# BBB_Breakout.net
KiCad netlist of a schematic drawn in EAGLE
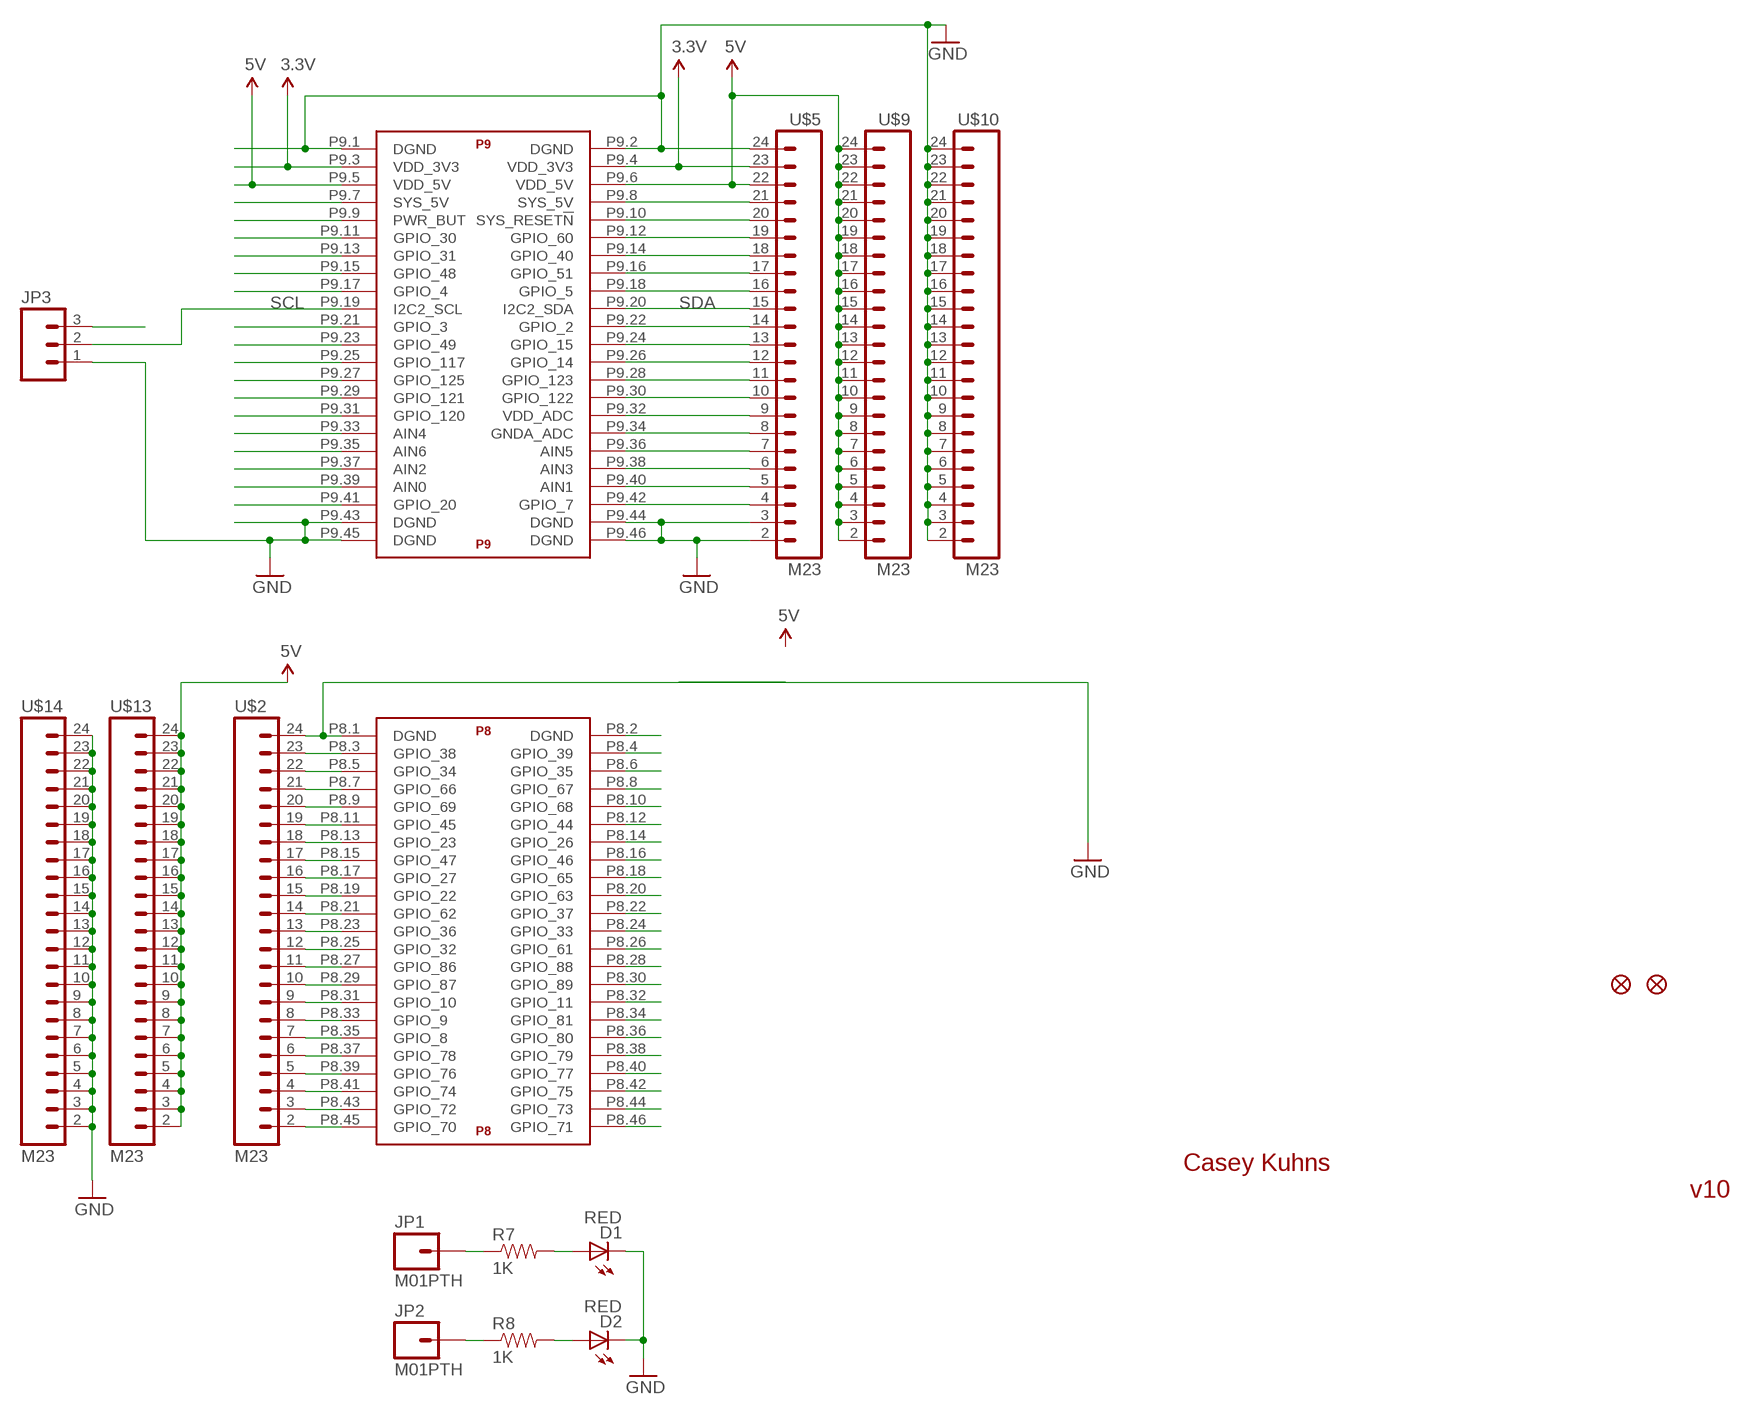
[diagram p0: schematic, sheet 1]

(export (version "E")
  (design (tool "Eeschema 10.0.6"))
  (components
    (comp (ref "D1")
      (value "RED")
      (footprint "eagle-import:LED-0603")
      (libsource (lib "eagle-import") (part "LED-RED0603"))
    )
    (comp (ref "D2")
      (value "RED")
      (footprint "eagle-import:LED-0603")
      (libsource (lib "eagle-import") (part "LED-RED0603"))
    )
    (comp (ref "FID1")
      (value "FIDUCIAL1X2")
      (footprint "eagle-import:FIDUCIAL-1X2")
      (libsource (lib "eagle-import") (part "FIDUCIAL1X2"))
    )
    (comp (ref "FID2")
      (value "FIDUCIAL1X2")
      (footprint "eagle-import:FIDUCIAL-1X2")
      (libsource (lib "eagle-import") (part "FIDUCIAL1X2"))
    )
    (comp (ref "JP1")
      (value "M01PTH")
      (footprint "eagle-import:1X01")
      (libsource (lib "eagle-import") (part "M01PTH"))
    )
    (comp (ref "JP2")
      (value "M01PTH")
      (footprint "eagle-import:1X01")
      (libsource (lib "eagle-import") (part "M01PTH"))
    )
    (comp (ref "JP3")
      (value "M03PTH")
      (footprint "eagle-import:1X03")
      (libsource (lib "eagle-import") (part "M03PTH"))
    )
    (comp (ref "R7")
      (value "1K")
      (footprint "eagle-import:0603-RES")
      (libsource (lib "eagle-import") (part "1KOHM1/10W1%(0603)"))
    )
    (comp (ref "R8")
      (value "1K")
      (footprint "eagle-import:0603-RES")
      (libsource (lib "eagle-import") (part "1KOHM1/10W1%(0603)"))
    )
    (comp (ref "U$1")
      (value "BEAGLE_BONE_BLACK_CAPE")
      (footprint "eagle-import:BEAGLE_BONE_BLACK_CAPE")
      (libsource (lib "eagle-import") (part "BEAGLE_BONE_BLACK_CAPE"))
    )
    (comp (ref "U$2")
      (value "M23")
      (footprint "eagle-import:1X23")
      (libsource (lib "eagle-import") (part "M23"))
    )
    (comp (ref "U$5")
      (value "M23")
      (footprint "eagle-import:1X23")
      (libsource (lib "eagle-import") (part "M23"))
    )
    (comp (ref "U$9")
      (value "M23")
      (footprint "eagle-import:1X23")
      (libsource (lib "eagle-import") (part "M23"))
    )
    (comp (ref "U$10")
      (value "M23")
      (footprint "eagle-import:1X23")
      (libsource (lib "eagle-import") (part "M23"))
    )
    (comp (ref "U$13")
      (value "M23")
      (footprint "eagle-import:1X23")
      (libsource (lib "eagle-import") (part "M23"))
    )
    (comp (ref "U$14")
      (value "M23")
      (footprint "eagle-import:1X23")
      (libsource (lib "eagle-import") (part "M23"))
    )
  )
  (nets
    (net (code "1") (name "/SCL") (class "Default")
      (node (ref "JP3") (pin "2") (pinfunction "2_2") (pintype "passive"))
      (node (ref "U$1") (pin "P9.19") (pinfunction "I2C2_SCL_P9.19") (pintype "bidirectional"))
    )
    (net (code "2") (name "/SDA") (class "Default")
      (node (ref "JP3") (pin "3") (pinfunction "3_3") (pintype "passive"))
      (node (ref "U$1") (pin "P9.20") (pinfunction "I2C2_SDA_P9.20") (pintype "bidirectional"))
      (node (ref "U$5") (pin "15") (pinfunction "15_15") (pintype "passive"))
    )
    (net (code "3") (name "3.3V") (class "Default")
      (node (ref "U$1") (pin "P9.3") (pinfunction "VDD_3V3_P9.3") (pintype "bidirectional"))
      (node (ref "U$1") (pin "P9.4") (pinfunction "VDD_3V3_P9.4") (pintype "bidirectional"))
      (node (ref "U$5") (pin "23") (pinfunction "23_23") (pintype "passive"))
    )
    (net (code "4") (name "5V") (class "Default")
      (node (ref "U$1") (pin "P9.5") (pinfunction "VDD_5V_P9.5") (pintype "bidirectional"))
      (node (ref "U$1") (pin "P9.6") (pinfunction "VDD_5V_P9.6") (pintype "bidirectional"))
      (node (ref "U$13") (pin "10") (pinfunction "10_10") (pintype "passive"))
      (node (ref "U$13") (pin "11") (pinfunction "11_11") (pintype "passive"))
      (node (ref "U$13") (pin "12") (pinfunction "12_12") (pintype "passive"))
      (node (ref "U$13") (pin "13") (pinfunction "13_13") (pintype "passive"))
      (node (ref "U$13") (pin "14") (pinfunction "14_14") (pintype "passive"))
      (node (ref "U$13") (pin "15") (pinfunction "15_15") (pintype "passive"))
      (node (ref "U$13") (pin "16") (pinfunction "16_16") (pintype "passive"))
      (node (ref "U$13") (pin "17") (pinfunction "17_17") (pintype "passive"))
      (node (ref "U$13") (pin "18") (pinfunction "18_18") (pintype "passive"))
      (node (ref "U$13") (pin "19") (pinfunction "19_19") (pintype "passive"))
      (node (ref "U$13") (pin "2") (pinfunction "2_2") (pintype "passive"))
      (node (ref "U$13") (pin "20") (pinfunction "20_20") (pintype "passive"))
      (node (ref "U$13") (pin "21") (pinfunction "21_21") (pintype "passive"))
      (node (ref "U$13") (pin "22") (pinfunction "22_22") (pintype "passive"))
      (node (ref "U$13") (pin "23") (pinfunction "23_23") (pintype "passive"))
      (node (ref "U$13") (pin "24") (pinfunction "24_24") (pintype "passive"))
      (node (ref "U$13") (pin "3") (pinfunction "3_3") (pintype "passive"))
      (node (ref "U$13") (pin "4") (pinfunction "4_4") (pintype "passive"))
      (node (ref "U$13") (pin "5") (pinfunction "5_5") (pintype "passive"))
      (node (ref "U$13") (pin "6") (pinfunction "6_6") (pintype "passive"))
      (node (ref "U$13") (pin "7") (pinfunction "7_7") (pintype "passive"))
      (node (ref "U$13") (pin "8") (pinfunction "8_8") (pintype "passive"))
      (node (ref "U$13") (pin "9") (pinfunction "9_9") (pintype "passive"))
      (node (ref "U$5") (pin "22") (pinfunction "22_22") (pintype "passive"))
      (node (ref "U$9") (pin "10") (pinfunction "10_10") (pintype "passive"))
      (node (ref "U$9") (pin "11") (pinfunction "11_11") (pintype "passive"))
      (node (ref "U$9") (pin "12") (pinfunction "12_12") (pintype "passive"))
      (node (ref "U$9") (pin "13") (pinfunction "13_13") (pintype "passive"))
      (node (ref "U$9") (pin "14") (pinfunction "14_14") (pintype "passive"))
      (node (ref "U$9") (pin "15") (pinfunction "15_15") (pintype "passive"))
      (node (ref "U$9") (pin "16") (pinfunction "16_16") (pintype "passive"))
      (node (ref "U$9") (pin "17") (pinfunction "17_17") (pintype "passive"))
      (node (ref "U$9") (pin "18") (pinfunction "18_18") (pintype "passive"))
      (node (ref "U$9") (pin "19") (pinfunction "19_19") (pintype "passive"))
      (node (ref "U$9") (pin "2") (pinfunction "2_2") (pintype "passive"))
      (node (ref "U$9") (pin "20") (pinfunction "20_20") (pintype "passive"))
      (node (ref "U$9") (pin "21") (pinfunction "21_21") (pintype "passive"))
      (node (ref "U$9") (pin "22") (pinfunction "22_22") (pintype "passive"))
      (node (ref "U$9") (pin "23") (pinfunction "23_23") (pintype "passive"))
      (node (ref "U$9") (pin "24") (pinfunction "24_24") (pintype "passive"))
      (node (ref "U$9") (pin "3") (pinfunction "3_3") (pintype "passive"))
      (node (ref "U$9") (pin "4") (pinfunction "4_4") (pintype "passive"))
      (node (ref "U$9") (pin "5") (pinfunction "5_5") (pintype "passive"))
      (node (ref "U$9") (pin "6") (pinfunction "6_6") (pintype "passive"))
      (node (ref "U$9") (pin "7") (pinfunction "7_7") (pintype "passive"))
      (node (ref "U$9") (pin "8") (pinfunction "8_8") (pintype "passive"))
      (node (ref "U$9") (pin "9") (pinfunction "9_9") (pintype "passive"))
    )
    (net (code "5") (name "GND") (class "Default")
      (node (ref "D1") (pin "C") (pinfunction "C_C") (pintype "passive"))
      (node (ref "D2") (pin "C") (pinfunction "C_C") (pintype "passive"))
      (node (ref "JP3") (pin "1") (pinfunction "1_1") (pintype "passive"))
      (node (ref "U$1") (pin "P8.1") (pinfunction "DGND_P8.1") (pintype "bidirectional"))
      (node (ref "U$1") (pin "P9.1") (pinfunction "DGND_P9.1") (pintype "bidirectional"))
      (node (ref "U$1") (pin "P9.2") (pinfunction "DGND_P9.2") (pintype "bidirectional"))
      (node (ref "U$1") (pin "P9.43") (pinfunction "DGND_P9.43") (pintype "bidirectional"))
      (node (ref "U$1") (pin "P9.44") (pinfunction "DGND_P9.44") (pintype "bidirectional"))
      (node (ref "U$1") (pin "P9.45") (pinfunction "DGND_P9.45") (pintype "bidirectional"))
      (node (ref "U$1") (pin "P9.46") (pinfunction "DGND_P9.46") (pintype "bidirectional"))
      (node (ref "U$10") (pin "10") (pinfunction "10_10") (pintype "passive"))
      (node (ref "U$10") (pin "11") (pinfunction "11_11") (pintype "passive"))
      (node (ref "U$10") (pin "12") (pinfunction "12_12") (pintype "passive"))
      (node (ref "U$10") (pin "13") (pinfunction "13_13") (pintype "passive"))
      (node (ref "U$10") (pin "14") (pinfunction "14_14") (pintype "passive"))
      (node (ref "U$10") (pin "15") (pinfunction "15_15") (pintype "passive"))
      (node (ref "U$10") (pin "16") (pinfunction "16_16") (pintype "passive"))
      (node (ref "U$10") (pin "17") (pinfunction "17_17") (pintype "passive"))
      (node (ref "U$10") (pin "18") (pinfunction "18_18") (pintype "passive"))
      (node (ref "U$10") (pin "19") (pinfunction "19_19") (pintype "passive"))
      (node (ref "U$10") (pin "2") (pinfunction "2_2") (pintype "passive"))
      (node (ref "U$10") (pin "20") (pinfunction "20_20") (pintype "passive"))
      (node (ref "U$10") (pin "21") (pinfunction "21_21") (pintype "passive"))
      (node (ref "U$10") (pin "22") (pinfunction "22_22") (pintype "passive"))
      (node (ref "U$10") (pin "23") (pinfunction "23_23") (pintype "passive"))
      (node (ref "U$10") (pin "24") (pinfunction "24_24") (pintype "passive"))
      (node (ref "U$10") (pin "3") (pinfunction "3_3") (pintype "passive"))
      (node (ref "U$10") (pin "4") (pinfunction "4_4") (pintype "passive"))
      (node (ref "U$10") (pin "5") (pinfunction "5_5") (pintype "passive"))
      (node (ref "U$10") (pin "6") (pinfunction "6_6") (pintype "passive"))
      (node (ref "U$10") (pin "7") (pinfunction "7_7") (pintype "passive"))
      (node (ref "U$10") (pin "8") (pinfunction "8_8") (pintype "passive"))
      (node (ref "U$10") (pin "9") (pinfunction "9_9") (pintype "passive"))
      (node (ref "U$14") (pin "10") (pinfunction "10_10") (pintype "passive"))
      (node (ref "U$14") (pin "11") (pinfunction "11_11") (pintype "passive"))
      (node (ref "U$14") (pin "12") (pinfunction "12_12") (pintype "passive"))
      (node (ref "U$14") (pin "13") (pinfunction "13_13") (pintype "passive"))
      (node (ref "U$14") (pin "14") (pinfunction "14_14") (pintype "passive"))
      (node (ref "U$14") (pin "15") (pinfunction "15_15") (pintype "passive"))
      (node (ref "U$14") (pin "16") (pinfunction "16_16") (pintype "passive"))
      (node (ref "U$14") (pin "17") (pinfunction "17_17") (pintype "passive"))
      (node (ref "U$14") (pin "18") (pinfunction "18_18") (pintype "passive"))
      (node (ref "U$14") (pin "19") (pinfunction "19_19") (pintype "passive"))
      (node (ref "U$14") (pin "2") (pinfunction "2_2") (pintype "passive"))
      (node (ref "U$14") (pin "20") (pinfunction "20_20") (pintype "passive"))
      (node (ref "U$14") (pin "21") (pinfunction "21_21") (pintype "passive"))
      (node (ref "U$14") (pin "22") (pinfunction "22_22") (pintype "passive"))
      (node (ref "U$14") (pin "23") (pinfunction "23_23") (pintype "passive"))
      (node (ref "U$14") (pin "24") (pinfunction "24_24") (pintype "passive"))
      (node (ref "U$14") (pin "3") (pinfunction "3_3") (pintype "passive"))
      (node (ref "U$14") (pin "4") (pinfunction "4_4") (pintype "passive"))
      (node (ref "U$14") (pin "5") (pinfunction "5_5") (pintype "passive"))
      (node (ref "U$14") (pin "6") (pinfunction "6_6") (pintype "passive"))
      (node (ref "U$14") (pin "7") (pinfunction "7_7") (pintype "passive"))
      (node (ref "U$14") (pin "8") (pinfunction "8_8") (pintype "passive"))
      (node (ref "U$14") (pin "9") (pinfunction "9_9") (pintype "passive"))
      (node (ref "U$2") (pin "24") (pinfunction "24_24") (pintype "passive"))
      (node (ref "U$5") (pin "2") (pinfunction "2_2") (pintype "passive"))
      (node (ref "U$5") (pin "24") (pinfunction "24_24") (pintype "passive"))
      (node (ref "U$5") (pin "3") (pinfunction "3_3") (pintype "passive"))
    )
    (net (code "6") (name "Net-(D1-PadA)") (class "Default")
      (node (ref "D1") (pin "A") (pinfunction "A_A") (pintype "passive"))
      (node (ref "R7") (pin "2") (pinfunction "2_2") (pintype "passive"))
    )
    (net (code "7") (name "Net-(D2-PadA)") (class "Default")
      (node (ref "D2") (pin "A") (pinfunction "A_A") (pintype "passive"))
      (node (ref "R8") (pin "2") (pinfunction "2_2") (pintype "passive"))
    )
    (net (code "8") (name "Net-(JP1-Pad1)") (class "Default")
      (node (ref "JP1") (pin "1") (pinfunction "1_1") (pintype "passive"))
      (node (ref "R7") (pin "1") (pinfunction "1_1") (pintype "passive"))
    )
    (net (code "9") (name "Net-(JP2-Pad1)") (class "Default")
      (node (ref "JP2") (pin "1") (pinfunction "1_1") (pintype "passive"))
      (node (ref "R8") (pin "1") (pinfunction "1_1") (pintype "passive"))
    )
    (net (code "10") (name "Net-(U$1A-GPIO_8)") (class "Default")
      (node (ref "U$1") (pin "P8.35") (pinfunction "GPIO_8_P8.35") (pintype "bidirectional"))
      (node (ref "U$2") (pin "7") (pinfunction "7_7") (pintype "passive"))
    )
    (net (code "11") (name "Net-(U$1A-GPIO_9)") (class "Default")
      (node (ref "U$1") (pin "P8.33") (pinfunction "GPIO_9_P8.33") (pintype "bidirectional"))
      (node (ref "U$2") (pin "8") (pinfunction "8_8") (pintype "passive"))
    )
    (net (code "12") (name "Net-(U$1A-GPIO_10)") (class "Default")
      (node (ref "U$1") (pin "P8.31") (pinfunction "GPIO_10_P8.31") (pintype "bidirectional"))
      (node (ref "U$2") (pin "9") (pinfunction "9_9") (pintype "passive"))
    )
    (net (code "13") (name "Net-(U$1A-GPIO_22)") (class "Default")
      (node (ref "U$1") (pin "P8.19") (pinfunction "GPIO_22_P8.19") (pintype "bidirectional"))
      (node (ref "U$2") (pin "15") (pinfunction "15_15") (pintype "passive"))
    )
    (net (code "14") (name "Net-(U$1A-GPIO_23)") (class "Default")
      (node (ref "U$1") (pin "P8.13") (pinfunction "GPIO_23_P8.13") (pintype "bidirectional"))
      (node (ref "U$2") (pin "18") (pinfunction "18_18") (pintype "passive"))
    )
    (net (code "15") (name "Net-(U$1A-GPIO_27)") (class "Default")
      (node (ref "U$1") (pin "P8.17") (pinfunction "GPIO_27_P8.17") (pintype "bidirectional"))
      (node (ref "U$2") (pin "16") (pinfunction "16_16") (pintype "passive"))
    )
    (net (code "16") (name "Net-(U$1A-GPIO_32)") (class "Default")
      (node (ref "U$1") (pin "P8.25") (pinfunction "GPIO_32_P8.25") (pintype "bidirectional"))
      (node (ref "U$2") (pin "12") (pinfunction "12_12") (pintype "passive"))
    )
    (net (code "17") (name "Net-(U$1A-GPIO_34)") (class "Default")
      (node (ref "U$1") (pin "P8.5") (pinfunction "GPIO_34_P8.5") (pintype "bidirectional"))
      (node (ref "U$2") (pin "22") (pinfunction "22_22") (pintype "passive"))
    )
    (net (code "18") (name "Net-(U$1A-GPIO_36)") (class "Default")
      (node (ref "U$1") (pin "P8.23") (pinfunction "GPIO_36_P8.23") (pintype "bidirectional"))
      (node (ref "U$2") (pin "13") (pinfunction "13_13") (pintype "passive"))
    )
    (net (code "19") (name "Net-(U$1A-GPIO_38)") (class "Default")
      (node (ref "U$1") (pin "P8.3") (pinfunction "GPIO_38_P8.3") (pintype "bidirectional"))
      (node (ref "U$2") (pin "23") (pinfunction "23_23") (pintype "passive"))
    )
    (net (code "20") (name "Net-(U$1A-GPIO_45)") (class "Default")
      (node (ref "U$1") (pin "P8.11") (pinfunction "GPIO_45_P8.11") (pintype "bidirectional"))
      (node (ref "U$2") (pin "19") (pinfunction "19_19") (pintype "passive"))
    )
    (net (code "21") (name "Net-(U$1A-GPIO_47)") (class "Default")
      (node (ref "U$1") (pin "P8.15") (pinfunction "GPIO_47_P8.15") (pintype "bidirectional"))
      (node (ref "U$2") (pin "17") (pinfunction "17_17") (pintype "passive"))
    )
    (net (code "22") (name "Net-(U$1A-GPIO_62)") (class "Default")
      (node (ref "U$1") (pin "P8.21") (pinfunction "GPIO_62_P8.21") (pintype "bidirectional"))
      (node (ref "U$2") (pin "14") (pinfunction "14_14") (pintype "passive"))
    )
    (net (code "23") (name "Net-(U$1A-GPIO_66)") (class "Default")
      (node (ref "U$1") (pin "P8.7") (pinfunction "GPIO_66_P8.7") (pintype "bidirectional"))
      (node (ref "U$2") (pin "21") (pinfunction "21_21") (pintype "passive"))
    )
    (net (code "24") (name "Net-(U$1A-GPIO_69)") (class "Default")
      (node (ref "U$1") (pin "P8.9") (pinfunction "GPIO_69_P8.9") (pintype "bidirectional"))
      (node (ref "U$2") (pin "20") (pinfunction "20_20") (pintype "passive"))
    )
    (net (code "25") (name "Net-(U$1A-GPIO_70)") (class "Default")
      (node (ref "U$1") (pin "P8.45") (pinfunction "GPIO_70_P8.45") (pintype "bidirectional"))
      (node (ref "U$2") (pin "2") (pinfunction "2_2") (pintype "passive"))
    )
    (net (code "26") (name "Net-(U$1A-GPIO_72)") (class "Default")
      (node (ref "U$1") (pin "P8.43") (pinfunction "GPIO_72_P8.43") (pintype "bidirectional"))
      (node (ref "U$2") (pin "3") (pinfunction "3_3") (pintype "passive"))
    )
    (net (code "27") (name "Net-(U$1A-GPIO_74)") (class "Default")
      (node (ref "U$1") (pin "P8.41") (pinfunction "GPIO_74_P8.41") (pintype "bidirectional"))
      (node (ref "U$2") (pin "4") (pinfunction "4_4") (pintype "passive"))
    )
    (net (code "28") (name "Net-(U$1A-GPIO_76)") (class "Default")
      (node (ref "U$1") (pin "P8.39") (pinfunction "GPIO_76_P8.39") (pintype "bidirectional"))
      (node (ref "U$2") (pin "5") (pinfunction "5_5") (pintype "passive"))
    )
    (net (code "29") (name "Net-(U$1A-GPIO_78)") (class "Default")
      (node (ref "U$1") (pin "P8.37") (pinfunction "GPIO_78_P8.37") (pintype "bidirectional"))
      (node (ref "U$2") (pin "6") (pinfunction "6_6") (pintype "passive"))
    )
    (net (code "30") (name "Net-(U$1A-GPIO_86)") (class "Default")
      (node (ref "U$1") (pin "P8.27") (pinfunction "GPIO_86_P8.27") (pintype "bidirectional"))
      (node (ref "U$2") (pin "11") (pinfunction "11_11") (pintype "passive"))
    )
    (net (code "31") (name "Net-(U$1A-GPIO_87)") (class "Default")
      (node (ref "U$1") (pin "P8.29") (pinfunction "GPIO_87_P8.29") (pintype "bidirectional"))
      (node (ref "U$2") (pin "10") (pinfunction "10_10") (pintype "passive"))
    )
    (net (code "32") (name "Net-(U$1B-AIN1)") (class "Default")
      (node (ref "U$1") (pin "P9.40") (pinfunction "AIN1_P9.40") (pintype "bidirectional"))
      (node (ref "U$5") (pin "5") (pinfunction "5_5") (pintype "passive"))
    )
    (net (code "33") (name "Net-(U$1B-AIN3)") (class "Default")
      (node (ref "U$1") (pin "P9.38") (pinfunction "AIN3_P9.38") (pintype "bidirectional"))
      (node (ref "U$5") (pin "6") (pinfunction "6_6") (pintype "passive"))
    )
    (net (code "34") (name "Net-(U$1B-AIN5)") (class "Default")
      (node (ref "U$1") (pin "P9.36") (pinfunction "AIN5_P9.36") (pintype "bidirectional"))
      (node (ref "U$5") (pin "7") (pinfunction "7_7") (pintype "passive"))
    )
    (net (code "35") (name "Net-(U$1B-GNDA_ADC)") (class "Default")
      (node (ref "U$1") (pin "P9.34") (pinfunction "GNDA_ADC_P9.34") (pintype "bidirectional"))
      (node (ref "U$5") (pin "8") (pinfunction "8_8") (pintype "passive"))
    )
    (net (code "36") (name "Net-(U$1B-GPIO_2)") (class "Default")
      (node (ref "U$1") (pin "P9.22") (pinfunction "GPIO_2_P9.22") (pintype "bidirectional"))
      (node (ref "U$5") (pin "14") (pinfunction "14_14") (pintype "passive"))
    )
    (net (code "37") (name "Net-(U$1B-GPIO_5)") (class "Default")
      (node (ref "U$1") (pin "P9.18") (pinfunction "GPIO_5_P9.18") (pintype "bidirectional"))
      (node (ref "U$5") (pin "16") (pinfunction "16_16") (pintype "passive"))
    )
    (net (code "38") (name "Net-(U$1B-GPIO_7)") (class "Default")
      (node (ref "U$1") (pin "P9.42") (pinfunction "GPIO_7_P9.42") (pintype "bidirectional"))
      (node (ref "U$5") (pin "4") (pinfunction "4_4") (pintype "passive"))
    )
    (net (code "39") (name "Net-(U$1B-GPIO_14)") (class "Default")
      (node (ref "U$1") (pin "P9.26") (pinfunction "GPIO_14_P9.26") (pintype "bidirectional"))
      (node (ref "U$5") (pin "12") (pinfunction "12_12") (pintype "passive"))
    )
    (net (code "40") (name "Net-(U$1B-GPIO_15)") (class "Default")
      (node (ref "U$1") (pin "P9.24") (pinfunction "GPIO_15_P9.24") (pintype "bidirectional"))
      (node (ref "U$5") (pin "13") (pinfunction "13_13") (pintype "passive"))
    )
    (net (code "41") (name "Net-(U$1B-GPIO_40)") (class "Default")
      (node (ref "U$1") (pin "P9.14") (pinfunction "GPIO_40_P9.14") (pintype "bidirectional"))
      (node (ref "U$5") (pin "18") (pinfunction "18_18") (pintype "passive"))
    )
    (net (code "42") (name "Net-(U$1B-GPIO_51)") (class "Default")
      (node (ref "U$1") (pin "P9.16") (pinfunction "GPIO_51_P9.16") (pintype "bidirectional"))
      (node (ref "U$5") (pin "17") (pinfunction "17_17") (pintype "passive"))
    )
    (net (code "43") (name "Net-(U$1B-GPIO_60)") (class "Default")
      (node (ref "U$1") (pin "P9.12") (pinfunction "GPIO_60_P9.12") (pintype "bidirectional"))
      (node (ref "U$5") (pin "19") (pinfunction "19_19") (pintype "passive"))
    )
    (net (code "44") (name "Net-(U$1B-GPIO_122)") (class "Default")
      (node (ref "U$1") (pin "P9.30") (pinfunction "GPIO_122_P9.30") (pintype "bidirectional"))
      (node (ref "U$5") (pin "10") (pinfunction "10_10") (pintype "passive"))
    )
    (net (code "45") (name "Net-(U$1B-GPIO_123)") (class "Default")
      (node (ref "U$1") (pin "P9.28") (pinfunction "GPIO_123_P9.28") (pintype "bidirectional"))
      (node (ref "U$5") (pin "11") (pinfunction "11_11") (pintype "passive"))
    )
    (net (code "46") (name "Net-(U$1B-SYS_5V-PadP9.8)") (class "Default")
      (node (ref "U$1") (pin "P9.8") (pinfunction "SYS_5V_P9.8") (pintype "bidirectional"))
      (node (ref "U$5") (pin "21") (pinfunction "21_21") (pintype "passive"))
    )
    (net (code "47") (name "Net-(U$1B-SYS_RESET~{N})") (class "Default")
      (node (ref "U$1") (pin "P9.10") (pinfunction "SYS_RESET~{N}_P9.10") (pintype "bidirectional"))
      (node (ref "U$5") (pin "20") (pinfunction "20_20") (pintype "passive"))
    )
    (net (code "48") (name "Net-(U$1B-VDD_ADC)") (class "Default")
      (node (ref "U$1") (pin "P9.32") (pinfunction "VDD_ADC_P9.32") (pintype "bidirectional"))
      (node (ref "U$5") (pin "9") (pinfunction "9_9") (pintype "passive"))
    )
    (net (code "49") (name "unconnected-(U$1A-DGND-PadP8.2)") (class "Default")
      (node (ref "U$1") (pin "P8.2") (pinfunction "DGND_P8.2") (pintype "bidirectional"))
    )
    (net (code "50") (name "unconnected-(U$1A-GPIO_11-PadP8.32)") (class "Default")
      (node (ref "U$1") (pin "P8.32") (pinfunction "GPIO_11_P8.32") (pintype "bidirectional"))
    )
    (net (code "51") (name "unconnected-(U$1A-GPIO_26-PadP8.14)") (class "Default")
      (node (ref "U$1") (pin "P8.14") (pinfunction "GPIO_26_P8.14") (pintype "bidirectional"))
    )
    (net (code "52") (name "unconnected-(U$1A-GPIO_33-PadP8.24)") (class "Default")
      (node (ref "U$1") (pin "P8.24") (pinfunction "GPIO_33_P8.24") (pintype "bidirectional"))
    )
    (net (code "53") (name "unconnected-(U$1A-GPIO_35-PadP8.6)") (class "Default")
      (node (ref "U$1") (pin "P8.6") (pinfunction "GPIO_35_P8.6") (pintype "bidirectional"))
    )
    (net (code "54") (name "unconnected-(U$1A-GPIO_37-PadP8.22)") (class "Default")
      (node (ref "U$1") (pin "P8.22") (pinfunction "GPIO_37_P8.22") (pintype "bidirectional"))
    )
    (net (code "55") (name "unconnected-(U$1A-GPIO_39-PadP8.4)") (class "Default")
      (node (ref "U$1") (pin "P8.4") (pinfunction "GPIO_39_P8.4") (pintype "bidirectional"))
    )
    (net (code "56") (name "unconnected-(U$1A-GPIO_44-PadP8.12)") (class "Default")
      (node (ref "U$1") (pin "P8.12") (pinfunction "GPIO_44_P8.12") (pintype "bidirectional"))
    )
    (net (code "57") (name "unconnected-(U$1A-GPIO_46-PadP8.16)") (class "Default")
      (node (ref "U$1") (pin "P8.16") (pinfunction "GPIO_46_P8.16") (pintype "bidirectional"))
    )
    (net (code "58") (name "unconnected-(U$1A-GPIO_61-PadP8.26)") (class "Default")
      (node (ref "U$1") (pin "P8.26") (pinfunction "GPIO_61_P8.26") (pintype "bidirectional"))
    )
    (net (code "59") (name "unconnected-(U$1A-GPIO_63-PadP8.20)") (class "Default")
      (node (ref "U$1") (pin "P8.20") (pinfunction "GPIO_63_P8.20") (pintype "bidirectional"))
    )
    (net (code "60") (name "unconnected-(U$1A-GPIO_65-PadP8.18)") (class "Default")
      (node (ref "U$1") (pin "P8.18") (pinfunction "GPIO_65_P8.18") (pintype "bidirectional"))
    )
    (net (code "61") (name "unconnected-(U$1A-GPIO_67-PadP8.8)") (class "Default")
      (node (ref "U$1") (pin "P8.8") (pinfunction "GPIO_67_P8.8") (pintype "bidirectional"))
    )
    (net (code "62") (name "unconnected-(U$1A-GPIO_68-PadP8.10)") (class "Default")
      (node (ref "U$1") (pin "P8.10") (pinfunction "GPIO_68_P8.10") (pintype "bidirectional"))
    )
    (net (code "63") (name "unconnected-(U$1A-GPIO_71-PadP8.46)") (class "Default")
      (node (ref "U$1") (pin "P8.46") (pinfunction "GPIO_71_P8.46") (pintype "bidirectional"))
    )
    (net (code "64") (name "unconnected-(U$1A-GPIO_73-PadP8.44)") (class "Default")
      (node (ref "U$1") (pin "P8.44") (pinfunction "GPIO_73_P8.44") (pintype "bidirectional"))
    )
    (net (code "65") (name "unconnected-(U$1A-GPIO_75-PadP8.42)") (class "Default")
      (node (ref "U$1") (pin "P8.42") (pinfunction "GPIO_75_P8.42") (pintype "bidirectional"))
    )
    (net (code "66") (name "unconnected-(U$1A-GPIO_77-PadP8.40)") (class "Default")
      (node (ref "U$1") (pin "P8.40") (pinfunction "GPIO_77_P8.40") (pintype "bidirectional"))
    )
    (net (code "67") (name "unconnected-(U$1A-GPIO_79-PadP8.38)") (class "Default")
      (node (ref "U$1") (pin "P8.38") (pinfunction "GPIO_79_P8.38") (pintype "bidirectional"))
    )
    (net (code "68") (name "unconnected-(U$1A-GPIO_80-PadP8.36)") (class "Default")
      (node (ref "U$1") (pin "P8.36") (pinfunction "GPIO_80_P8.36") (pintype "bidirectional"))
    )
    (net (code "69") (name "unconnected-(U$1A-GPIO_81-PadP8.34)") (class "Default")
      (node (ref "U$1") (pin "P8.34") (pinfunction "GPIO_81_P8.34") (pintype "bidirectional"))
    )
    (net (code "70") (name "unconnected-(U$1A-GPIO_88-PadP8.28)") (class "Default")
      (node (ref "U$1") (pin "P8.28") (pinfunction "GPIO_88_P8.28") (pintype "bidirectional"))
    )
    (net (code "71") (name "unconnected-(U$1A-GPIO_89-PadP8.30)") (class "Default")
      (node (ref "U$1") (pin "P8.30") (pinfunction "GPIO_89_P8.30") (pintype "bidirectional"))
    )
    (net (code "72") (name "unconnected-(U$1B-AIN0-PadP9.39)") (class "Default")
      (node (ref "U$1") (pin "P9.39") (pinfunction "AIN0_P9.39") (pintype "bidirectional"))
    )
    (net (code "73") (name "unconnected-(U$1B-AIN2-PadP9.37)") (class "Default")
      (node (ref "U$1") (pin "P9.37") (pinfunction "AIN2_P9.37") (pintype "bidirectional"))
    )
    (net (code "74") (name "unconnected-(U$1B-AIN4-PadP9.33)") (class "Default")
      (node (ref "U$1") (pin "P9.33") (pinfunction "AIN4_P9.33") (pintype "bidirectional"))
    )
    (net (code "75") (name "unconnected-(U$1B-AIN6-PadP9.35)") (class "Default")
      (node (ref "U$1") (pin "P9.35") (pinfunction "AIN6_P9.35") (pintype "bidirectional"))
    )
    (net (code "76") (name "unconnected-(U$1B-GPIO_3-PadP9.21)") (class "Default")
      (node (ref "U$1") (pin "P9.21") (pinfunction "GPIO_3_P9.21") (pintype "bidirectional"))
    )
    (net (code "77") (name "unconnected-(U$1B-GPIO_4-PadP9.17)") (class "Default")
      (node (ref "U$1") (pin "P9.17") (pinfunction "GPIO_4_P9.17") (pintype "bidirectional"))
    )
    (net (code "78") (name "unconnected-(U$1B-GPIO_20-PadP9.41)") (class "Default")
      (node (ref "U$1") (pin "P9.41") (pinfunction "GPIO_20_P9.41") (pintype "bidirectional"))
    )
    (net (code "79") (name "unconnected-(U$1B-GPIO_30-PadP9.11)") (class "Default")
      (node (ref "U$1") (pin "P9.11") (pinfunction "GPIO_30_P9.11") (pintype "bidirectional"))
    )
    (net (code "80") (name "unconnected-(U$1B-GPIO_31-PadP9.13)") (class "Default")
      (node (ref "U$1") (pin "P9.13") (pinfunction "GPIO_31_P9.13") (pintype "bidirectional"))
    )
    (net (code "81") (name "unconnected-(U$1B-GPIO_48-PadP9.15)") (class "Default")
      (node (ref "U$1") (pin "P9.15") (pinfunction "GPIO_48_P9.15") (pintype "bidirectional"))
    )
    (net (code "82") (name "unconnected-(U$1B-GPIO_49-PadP9.23)") (class "Default")
      (node (ref "U$1") (pin "P9.23") (pinfunction "GPIO_49_P9.23") (pintype "bidirectional"))
    )
    (net (code "83") (name "unconnected-(U$1B-GPIO_117-PadP9.25)") (class "Default")
      (node (ref "U$1") (pin "P9.25") (pinfunction "GPIO_117_P9.25") (pintype "bidirectional"))
    )
    (net (code "84") (name "unconnected-(U$1B-GPIO_120-PadP9.31)") (class "Default")
      (node (ref "U$1") (pin "P9.31") (pinfunction "GPIO_120_P9.31") (pintype "bidirectional"))
    )
    (net (code "85") (name "unconnected-(U$1B-GPIO_121-PadP9.29)") (class "Default")
      (node (ref "U$1") (pin "P9.29") (pinfunction "GPIO_121_P9.29") (pintype "bidirectional"))
    )
    (net (code "86") (name "unconnected-(U$1B-GPIO_125-PadP9.27)") (class "Default")
      (node (ref "U$1") (pin "P9.27") (pinfunction "GPIO_125_P9.27") (pintype "bidirectional"))
    )
    (net (code "87") (name "unconnected-(U$1B-PWR_BUT-PadP9.9)") (class "Default")
      (node (ref "U$1") (pin "P9.9") (pinfunction "PWR_BUT_P9.9") (pintype "bidirectional"))
    )
    (net (code "88") (name "unconnected-(U$1B-SYS_5V-PadP9.7)") (class "Default")
      (node (ref "U$1") (pin "P9.7") (pinfunction "SYS_5V_P9.7") (pintype "bidirectional"))
    )
  )
)
